# Powersupply.net
KiCad netlist of a schematic drawn in Altium Designer
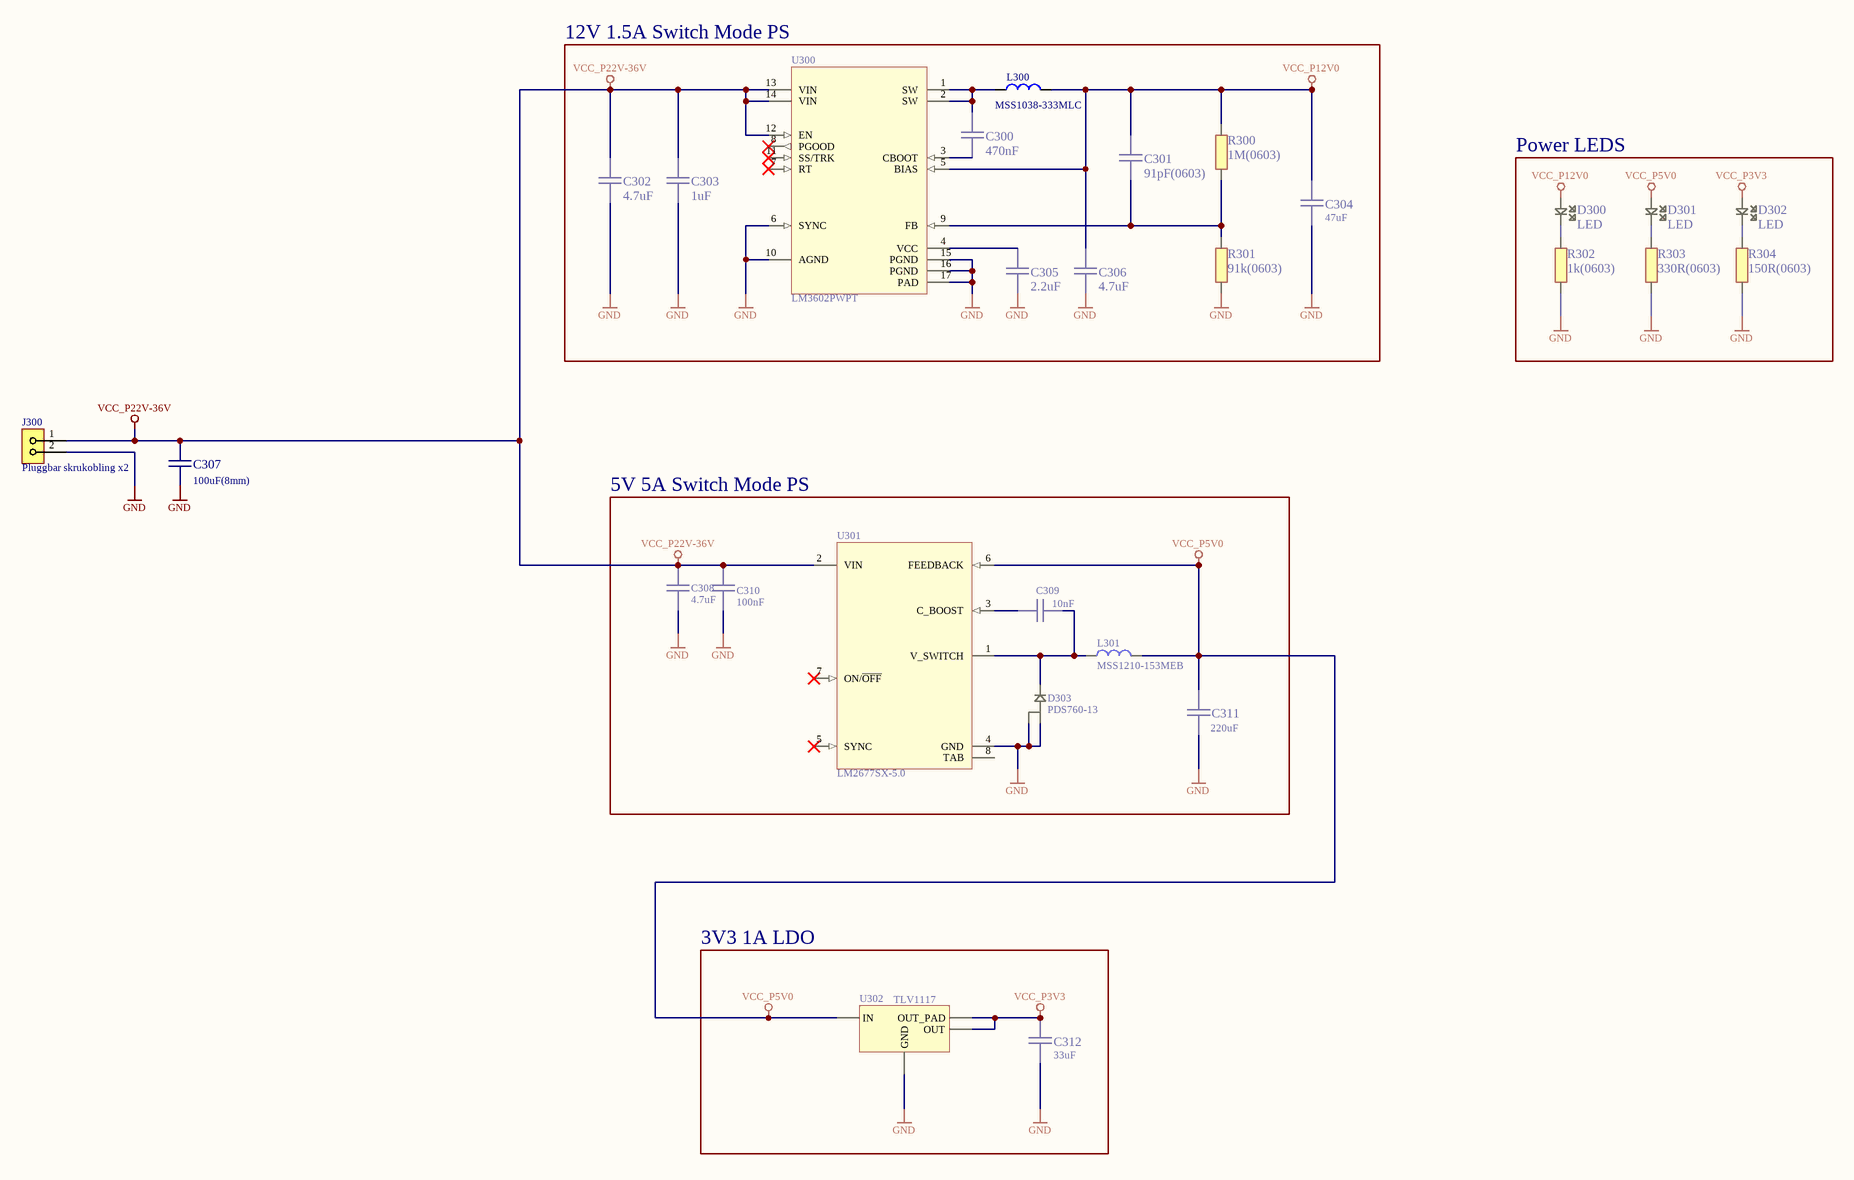
[diagram p0: Powersupply.SchDoc]

(export (version "E")
  (design (tool "Eeschema 10.0.6"))
  (components
    (comp (ref "C300")
      (value "470nF")
      (footprint "CAPC0805(2012)100_N")
      (description "470nF 0805 chip X7R 50V")
      (libsource (lib "OVLib") (part "CAP"))
    )
    (comp (ref "C301")
      (value "91pF(0603)")
      (footprint "CAPC0603(1608)55_N")
      (description "100nF 0603 5% NP0 50V")
      (libsource (lib "OVLib") (part "CAP"))
    )
    (comp (ref "C302")
      (value "4.7uF")
      (footprint "CAPC1206(3216)170_N")
      (description "100nF 1206 chip X7R 50V")
      (libsource (lib "OVLib") (part "CAP"))
    )
    (comp (ref "C303")
      (value "1uF")
      (footprint "CAPC1206(3216)170_N")
      (description "1uF 1206 chip X7R 50V")
      (libsource (lib "OVLib") (part "CAP"))
    )
    (comp (ref "C304")
      (value "T495D476M025ATE120")
      (footprint "CAPMP7342X30N")
      (fields (field (name "MANUFACTURER") "Kemet") (field (name "VERDI") "47uF"))
      (libsource (lib "T495D476M025ATE120") (part "T495D476M025ATE120"))
    )
    (comp (ref "C305")
      (value "2.2uF")
      (footprint "CAPC0603(1608)55_N")
      (description "2.2uF 0603 chip X7R 6.3V")
      (libsource (lib "OVLib") (part "CAP"))
    )
    (comp (ref "C306")
      (value "4.7uF")
      (footprint "CAPC1206(3216)170_N")
      (description "100nF 1206 chip X7R 50V")
      (libsource (lib "OVLib") (part "CAP"))
    )
    (comp (ref "C307")
      (value "100uF(8mm)")
      (footprint "CAPPR35D08H11")
      (description "D=8mm Radial, 20% 50V 3,5mm pitch")
      (libsource (lib "OVLib") (part "CAP"))
    )
    (comp (ref "C308")
      (value "4.7uF")
      (footprint "CAPC1206(3216)170_N")
      (description "100nF 1206 chip X7R 50V")
      (libsource (lib "OVLib") (part "CAP"))
    )
    (comp (ref "C309")
      (value "10nF")
      (footprint "CAPC0805(2012)100_N")
      (description "100nF 0805 chip X7R 50V")
      (libsource (lib "OVLib") (part "CAP"))
    )
    (comp (ref "C310")
      (value "100nF")
      (footprint "CAPC0805(2012)100_N")
      (description "100nF 0805 chip X7R 50V")
      (libsource (lib "OVLib") (part "CAP"))
    )
    (comp (ref "C311")
      (value "10TPB220ML")
      (footprint "CAPMP7342X30N")
      (fields (field (name "VERDI") "220uF"))
      (libsource (lib "10TPB220ML") (part "10TPB220ML"))
    )
    (comp (ref "C312")
      (value "10TPB33M")
      (footprint "CAPMP7342X30N")
      (fields (field (name "VERDI") "33uF"))
      (libsource (lib "10TPB33M") (part "10TPB33M"))
    )
    (comp (ref "D300")
      (value "LED")
      (footprint "I_LEDC0603(1608)_N")
      (description "SMD")
      (libsource (lib "OVLib") (part "LED"))
    )
    (comp (ref "D301")
      (value "LED")
      (footprint "I_LEDC0603(1608)_N")
      (description "SMD")
      (libsource (lib "OVLib") (part "LED"))
    )
    (comp (ref "D302")
      (value "LED")
      (footprint "I_LEDC0603(1608)_N")
      (description "SMD")
      (libsource (lib "OVLib") (part "LED"))
    )
    (comp (ref "D303")
      (value "PDS760-13")
      (footprint "DFN540P650X115-3N")
      (description "SCHOTTKY RECTIFIER POWERDI5")
      (libsource (lib "PDS760-13") (part "PDS760-13"))
    )
    (comp (ref "J300")
      (value "Pluggbar skrukobling x2")
      (footprint "FCI-20020110-C021A01LF")
      (description "Skruplint")
      (libsource (lib "OVLib") (part "Header1x2"))
    )
    (comp (ref "L300")
      (value "MSS1038-333MLC")
      (footprint "INDP102100X40N")
      (description "INDUCTOR, PWR, 33UH, 2.3A, 20%,13MHZ")
      (libsource (lib "MSS1038-333MLC") (part "MSS1038-333MLC"))
    )
    (comp (ref "L301")
      (value "MSS1210-153MEB")
      (footprint "INDP123123X100N")
      (description "INDUCTOR, PWR, 15UH, 8.7A, 20%,12MHZ")
      (libsource (lib "MSS1210-153MEB") (part "MSS1210-153MEB"))
    )
    (comp (ref "R300")
      (value "1M(0603)")
      (footprint "RESC0603(1608)_N")
      (description "0603 0.1W 1% Thick film resistor")
      (libsource (lib "OVLib") (part "Resistor2"))
    )
    (comp (ref "R301")
      (value "91k(0603)")
      (footprint "RESC0603(1608)_N")
      (description "91k 0603 0.1W 1% Thick film resistor")
      (libsource (lib "OVLib") (part "Resistor2"))
    )
    (comp (ref "R302")
      (value "1k(0603)")
      (footprint "RESC0603(1608)_N")
      (description "0603 0.1W 1% Thick film resistor")
      (libsource (lib "OVLib") (part "Resistor2"))
    )
    (comp (ref "R303")
      (value "330R(0603)")
      (footprint "RESC0603(1608)_N")
      (description "330R 0603 0.1W 1% Thick film resistor")
      (libsource (lib "OVLib") (part "Resistor2"))
    )
    (comp (ref "R304")
      (value "150R(0603)")
      (footprint "RESC0603(1608)_N")
      (description "0603 0.1W 1% Thick film resistor")
      (libsource (lib "OVLib") (part "Resistor2"))
    )
    (comp (ref "U300")
      (value "LM3602PWPT")
      (footprint "HTSSOP65P640X120_HS-17N")
      (fields (field (name "MPN") "LM43602PWPT") (field (name "MANUFACTURER") "Texas Instruments"))
      (libsource (lib "LM43602PWPT") (part "LM3602PWPT"))
    )
    (comp (ref "U301")
      (value "LM2677SX-5.0")
      (footprint "DPAK127P1336X457-8N")
      (libsource (lib "LM2677SX-5.0") (part "LM2677SX-5.0"))
    )
    (comp (ref "U302")
      (value "TLV1117")
      (footprint "SOT230P700X180-4N")
      (description "Low dropout regulator")
      (libsource (lib "OVLib") (part "LDO_REGULATOR"))
    )
  )
  (nets
    (net (code "1") (name "GND") (class "Default")
      (node (ref "C302") (pin "1") (pinfunction "1_1") (pintype "passive"))
      (node (ref "C303") (pin "1") (pinfunction "1_1") (pintype "passive"))
      (node (ref "C304") (pin "1") (pinfunction "1_1") (pintype "passive"))
      (node (ref "C305") (pin "1") (pinfunction "1_1") (pintype "passive"))
      (node (ref "C306") (pin "1") (pinfunction "1_1") (pintype "passive"))
      (node (ref "C307") (pin "1") (pinfunction "1_1") (pintype "passive"))
      (node (ref "C308") (pin "1") (pinfunction "1_1") (pintype "passive"))
      (node (ref "C310") (pin "1") (pinfunction "1_1") (pintype "passive"))
      (node (ref "C311") (pin "1") (pinfunction "1_1") (pintype "passive"))
      (node (ref "C312") (pin "1") (pinfunction "1_1") (pintype "passive"))
      (node (ref "D303") (pin "1") (pinfunction "A_1") (pintype "passive"))
      (node (ref "D303") (pin "2") (pinfunction "A_2") (pintype "passive"))
      (node (ref "J300") (pin "2") (pinfunction "2_2") (pintype "passive"))
      (node (ref "R301") (pin "1") (pinfunction "1_1") (pintype "passive"))
      (node (ref "R302") (pin "1") (pinfunction "1_1") (pintype "passive"))
      (node (ref "R303") (pin "1") (pinfunction "1_1") (pintype "passive"))
      (node (ref "R304") (pin "1") (pinfunction "1_1") (pintype "passive"))
      (node (ref "U300") (pin "10") (pinfunction "AGND_10") (pintype "power_in"))
      (node (ref "U300") (pin "15") (pinfunction "PGND_15") (pintype "power_in"))
      (node (ref "U300") (pin "16") (pinfunction "PGND_16") (pintype "power_in"))
      (node (ref "U300") (pin "17") (pinfunction "PAD_17") (pintype "power_in"))
      (node (ref "U300") (pin "6") (pinfunction "SYNC_6") (pintype "input"))
      (node (ref "U301") (pin "4") (pinfunction "GND_4") (pintype "power_in"))
      (node (ref "U302") (pin "1") (pinfunction "GND_1") (pintype "power_in"))
    )
    (net (code "2") (name "Net-(C300-Pad2)") (class "Default")
      (node (ref "C300") (pin "2") (pinfunction "2_2") (pintype "passive"))
      (node (ref "L300") (pin "1") (pinfunction "1_1") (pintype "passive"))
      (node (ref "U300") (pin "1") (pinfunction "SW_1") (pintype "power_in"))
      (node (ref "U300") (pin "2") (pinfunction "SW_2") (pintype "power_in"))
    )
    (net (code "3") (name "Net-(D300-Pad2)") (class "Default")
      (node (ref "D300") (pin "2") (pinfunction "2_2") (pintype "passive"))
      (node (ref "R302") (pin "2") (pinfunction "2_2") (pintype "passive"))
    )
    (net (code "4") (name "Net-(D301-Pad2)") (class "Default")
      (node (ref "D301") (pin "2") (pinfunction "2_2") (pintype "passive"))
      (node (ref "R303") (pin "2") (pinfunction "2_2") (pintype "passive"))
    )
    (net (code "5") (name "Net-(D302-Pad2)") (class "Default")
      (node (ref "D302") (pin "2") (pinfunction "2_2") (pintype "passive"))
      (node (ref "R304") (pin "2") (pinfunction "2_2") (pintype "passive"))
    )
    (net (code "6") (name "Net-(D303-K)") (class "Default")
      (node (ref "C309") (pin "2") (pinfunction "2_2") (pintype "passive"))
      (node (ref "D303") (pin "3") (pinfunction "K_3") (pintype "passive"))
      (node (ref "L301") (pin "1") (pinfunction "1_1") (pintype "passive"))
      (node (ref "U301") (pin "1") (pinfunction "V_SWITCH_1") (pintype "power_in"))
    )
    (net (code "7") (name "Net-(U300-CBOOT)") (class "Default")
      (node (ref "C300") (pin "1") (pinfunction "1_1") (pintype "passive"))
      (node (ref "U300") (pin "3") (pinfunction "CBOOT_3") (pintype "input"))
    )
    (net (code "8") (name "Net-(U300-FB)") (class "Default")
      (node (ref "C301") (pin "1") (pinfunction "1_1") (pintype "passive"))
      (node (ref "R300") (pin "1") (pinfunction "1_1") (pintype "passive"))
      (node (ref "R301") (pin "2") (pinfunction "2_2") (pintype "passive"))
      (node (ref "U300") (pin "9") (pinfunction "FB_9") (pintype "input"))
    )
    (net (code "9") (name "Net-(U300-VCC)") (class "Default")
      (node (ref "C305") (pin "2") (pinfunction "2_2") (pintype "passive"))
      (node (ref "U300") (pin "4") (pinfunction "VCC_4") (pintype "power_in"))
    )
    (net (code "10") (name "Net-(U301-C_BOOST)") (class "Default")
      (node (ref "C309") (pin "1") (pinfunction "1_1") (pintype "passive"))
      (node (ref "U301") (pin "3") (pinfunction "C_BOOST_3") (pintype "input"))
    )
    (net (code "11") (name "VCC_P3V3") (class "Default")
      (node (ref "C312") (pin "2") (pinfunction "2_2") (pintype "passive"))
      (node (ref "D302") (pin "1") (pinfunction "1_1") (pintype "passive"))
      (node (ref "U302") (pin "2") (pinfunction "OUT_PAD_2") (pintype "power_in"))
      (node (ref "U302") (pin "4") (pinfunction "OUT_4") (pintype "power_in"))
    )
    (net (code "12") (name "VCC_P5V0") (class "Default")
      (node (ref "C311") (pin "2") (pinfunction "2_2") (pintype "passive"))
      (node (ref "D301") (pin "1") (pinfunction "1_1") (pintype "passive"))
      (node (ref "L301") (pin "2") (pinfunction "2_2") (pintype "passive"))
      (node (ref "U301") (pin "6") (pinfunction "FEEDBACK_6") (pintype "input"))
      (node (ref "U302") (pin "3") (pinfunction "IN_3") (pintype "power_in"))
    )
    (net (code "13") (name "VCC_P12V0") (class "Default")
      (node (ref "C301") (pin "2") (pinfunction "2_2") (pintype "passive"))
      (node (ref "C304") (pin "2") (pinfunction "2_2") (pintype "passive"))
      (node (ref "C306") (pin "2") (pinfunction "2_2") (pintype "passive"))
      (node (ref "D300") (pin "1") (pinfunction "1_1") (pintype "passive"))
      (node (ref "L300") (pin "2") (pinfunction "2_2") (pintype "passive"))
      (node (ref "R300") (pin "2") (pinfunction "2_2") (pintype "passive"))
      (node (ref "U300") (pin "5") (pinfunction "BIAS_5") (pintype "input"))
    )
    (net (code "14") (name "VCC_P22V-36V") (class "Default")
      (node (ref "C302") (pin "2") (pinfunction "2_2") (pintype "passive"))
      (node (ref "C303") (pin "2") (pinfunction "2_2") (pintype "passive"))
      (node (ref "C307") (pin "2") (pinfunction "2_2") (pintype "passive"))
      (node (ref "C308") (pin "2") (pinfunction "2_2") (pintype "passive"))
      (node (ref "C310") (pin "2") (pinfunction "2_2") (pintype "passive"))
      (node (ref "J300") (pin "1") (pinfunction "1_1") (pintype "passive"))
      (node (ref "U300") (pin "12") (pinfunction "EN_12") (pintype "input"))
      (node (ref "U300") (pin "13") (pinfunction "VIN_13") (pintype "power_in"))
      (node (ref "U300") (pin "14") (pinfunction "VIN_14") (pintype "power_in"))
      (node (ref "U301") (pin "2") (pinfunction "VIN_2") (pintype "power_in"))
    )
    (net (code "15") (name "unconnected-(U300-PGOOD-Pad8)") (class "Default")
      (node (ref "U300") (pin "8") (pinfunction "PGOOD_8") (pintype "output+no_connect"))
    )
    (net (code "16") (name "unconnected-(U300-RT-Pad7)") (class "Default")
      (node (ref "U300") (pin "7") (pinfunction "RT_7") (pintype "input+no_connect"))
    )
    (net (code "17") (name "unconnected-(U300-SS{slash}TRK-Pad11)") (class "Default")
      (node (ref "U300") (pin "11") (pinfunction "SS/TRK_11") (pintype "input+no_connect"))
    )
    (net (code "18") (name "unconnected-(U301-ON{slash}~{OFF}-Pad7)") (class "Default")
      (node (ref "U301") (pin "7") (pinfunction "ON/~{OFF}_7") (pintype "input+no_connect"))
    )
    (net (code "19") (name "unconnected-(U301-SYNC-Pad5)") (class "Default")
      (node (ref "U301") (pin "5") (pinfunction "SYNC_5") (pintype "input+no_connect"))
    )
    (net (code "20") (name "unconnected-(U301-TAB-Pad8)") (class "Default")
      (node (ref "U301") (pin "8") (pinfunction "TAB_8") (pintype "passive"))
    )
  )
)
